# SAM4S_MCU_Hat.net
KiCad netlist of a schematic drawn in Altium Designer
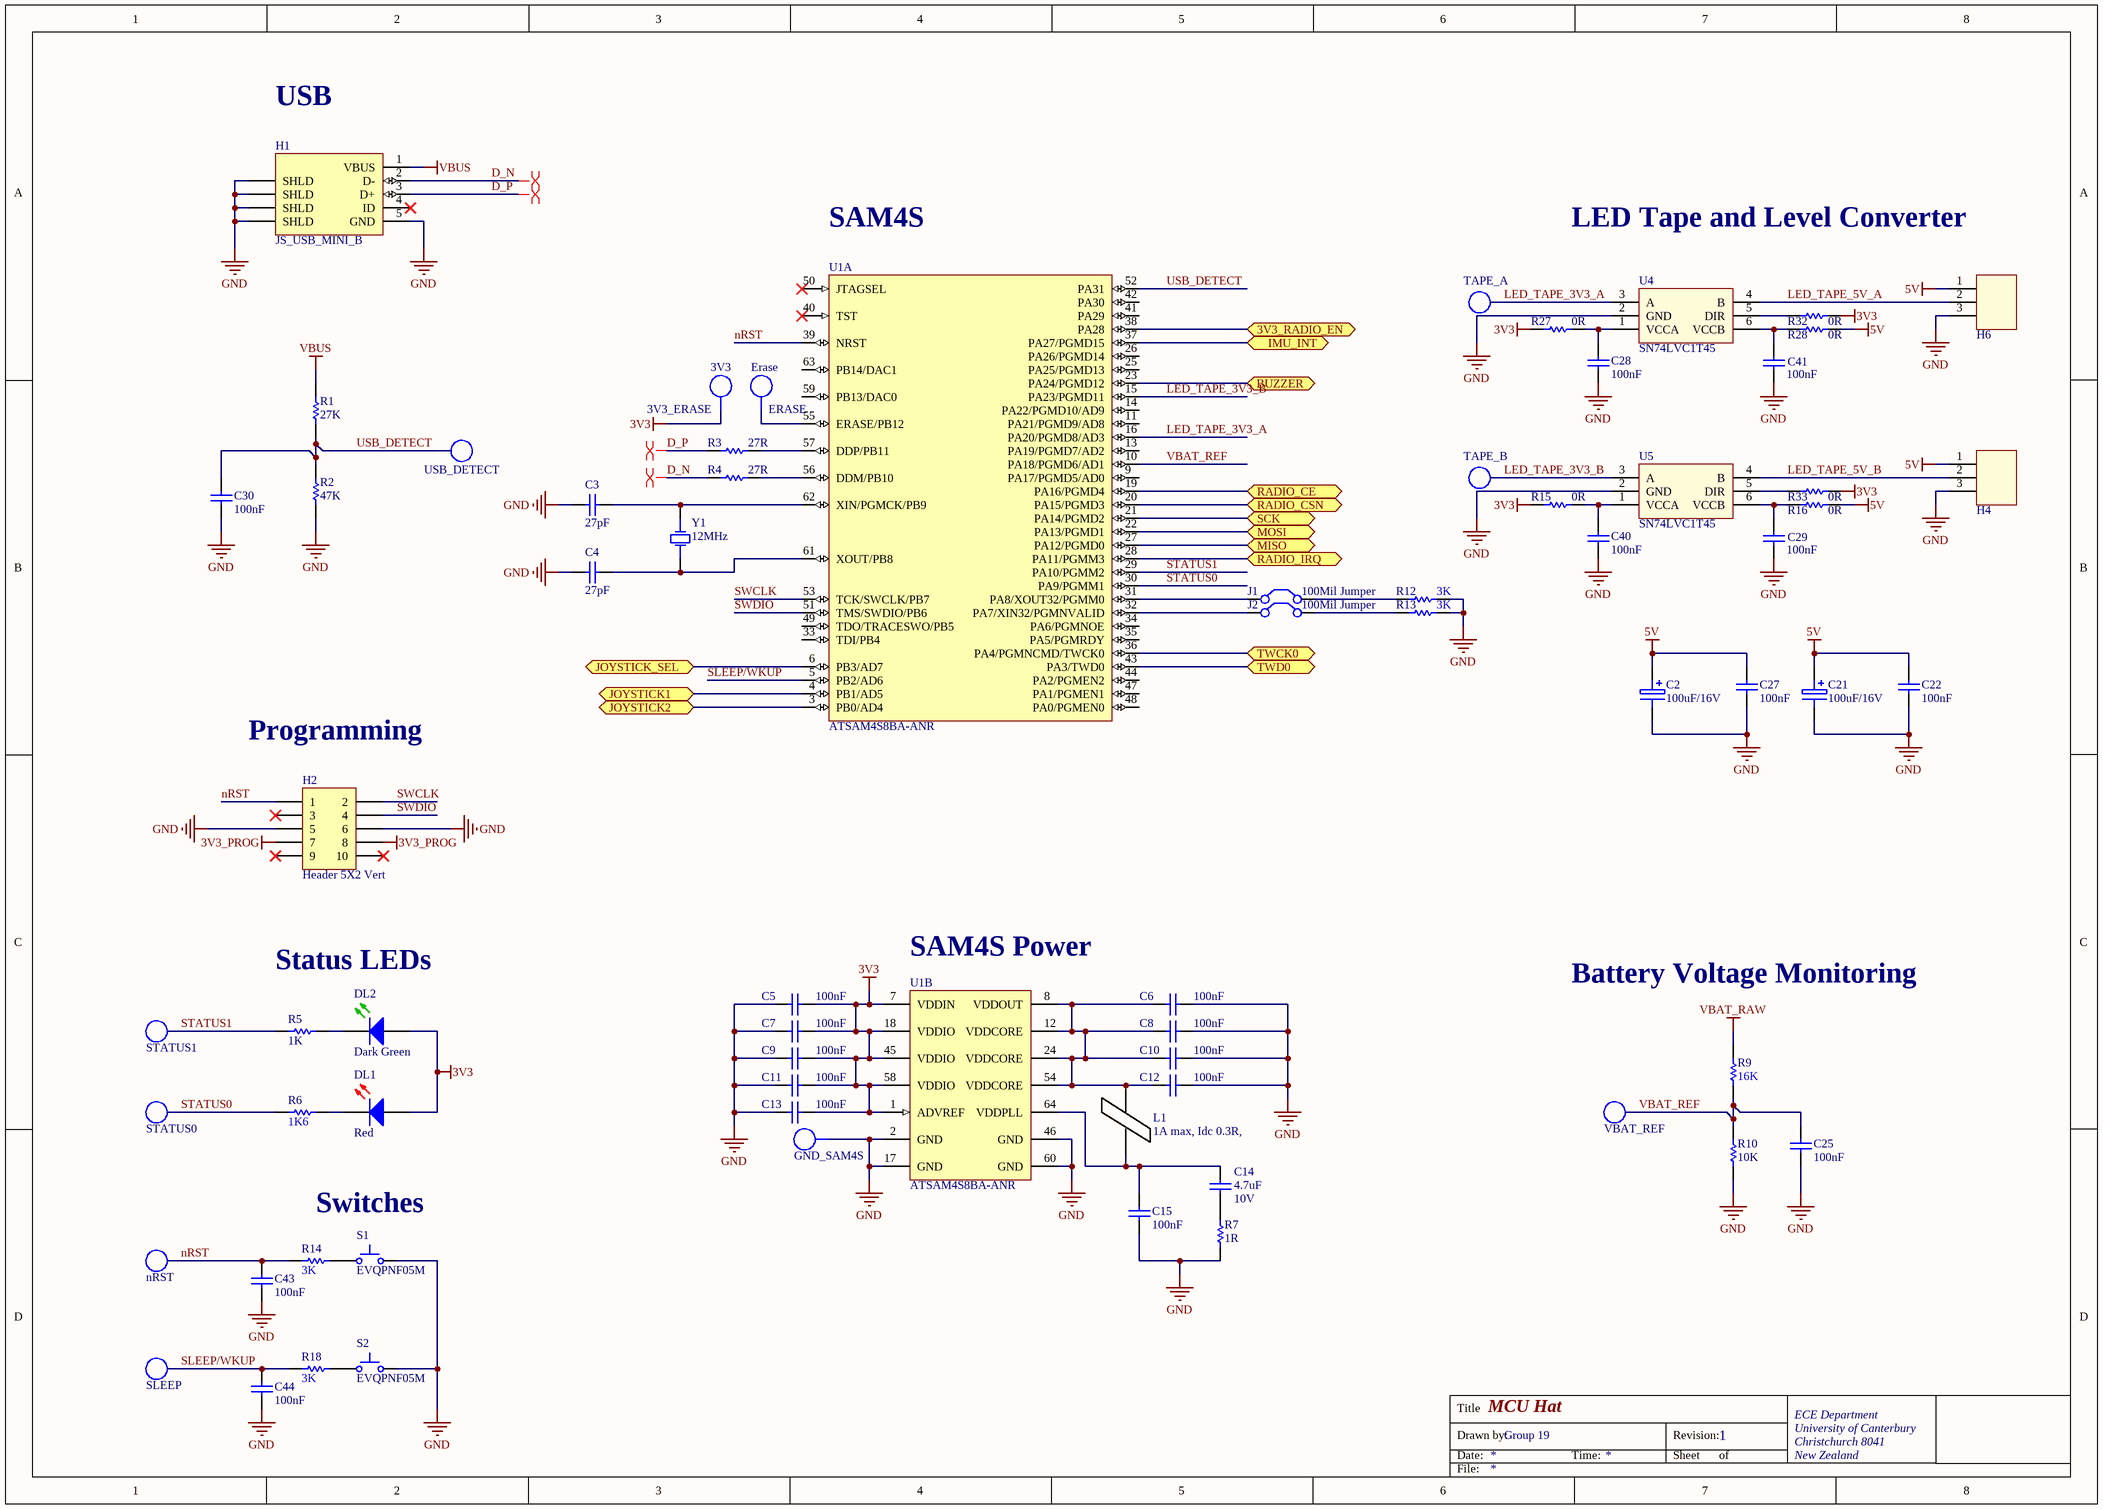
[diagram p0: SAM4S_MCU_Hat.SchDoc]

(export (version "E")
  (design (tool "Eeschema 10.0.6"))
  (components
    (comp (ref "3V3_ERASE")
      (value "3V3")
      (footprint "TP_1206")
      (description "Test-Point 3.3x1.6x2.1mm SMD")
      (fields
        (field (name "MANUFACTURER") "Harwin Inc")
        (field (name "MANUFACTURER PART NUMBER") "S1751-46R")
      )
      (libsource (lib "ECE AD19Components_19V1") (part "TP_1206"))
    )
    (comp (ref "C2")
      (value "100uF/16V")
      (footprint "NICH-1")
      (description "CAP ALUM 100uF 16V SMD")
      (fields (field (name "MANUFACTURER") "Nichcon"))
      (libsource (lib "ECE AD19Components_19V1") (part "CA_100uF_16V"))
    )
    (comp (ref "C3")
      (value "27pF")
      (footprint "CAPC1608L")
      (description "CAP CER 27pF NPO/COG +-5% 50V 0603")
      (libsource (lib "ECE AD19Components_19V1") (part "CC_27pF_0603"))
    )
    (comp (ref "C4")
      (value "27pF")
      (footprint "CAPC1608L")
      (description "CAP CER 27pF NPO/COG +-5% 50V 0603")
      (libsource (lib "ECE AD19Components_19V1") (part "CC_27pF_0603"))
    )
    (comp (ref "C5")
      (value "100nF")
      (footprint "CAPC1608L")
      (description "CAP CER 100nF X7R +-10% 50V 0603")
      (libsource (lib "ECE AD19Components_19V1") (part "CC_100nF_0603"))
    )
    (comp (ref "C6")
      (value "100nF")
      (footprint "CAPC1608L")
      (description "CAP CER 100nF X7R +-10% 50V 0603")
      (libsource (lib "ECE AD19Components_19V1") (part "CC_100nF_0603"))
    )
    (comp (ref "C7")
      (value "100nF")
      (footprint "CAPC1608L")
      (description "CAP CER 100nF X7R +-10% 50V 0603")
      (libsource (lib "ECE AD19Components_19V1") (part "CC_100nF_0603"))
    )
    (comp (ref "C8")
      (value "100nF")
      (footprint "CAPC1608L")
      (description "CAP CER 100nF X7R +-10% 50V 0603")
      (libsource (lib "ECE AD19Components_19V1") (part "CC_100nF_0603"))
    )
    (comp (ref "C9")
      (value "100nF")
      (footprint "CAPC1608L")
      (description "CAP CER 100nF X7R +-10% 50V 0603")
      (libsource (lib "ECE AD19Components_19V1") (part "CC_100nF_0603"))
    )
    (comp (ref "C10")
      (value "100nF")
      (footprint "CAPC1608L")
      (description "CAP CER 100nF X7R +-10% 50V 0603")
      (libsource (lib "ECE AD19Components_19V1") (part "CC_100nF_0603"))
    )
    (comp (ref "C11")
      (value "100nF")
      (footprint "CAPC1608L")
      (description "CAP CER 100nF X7R +-10% 50V 0603")
      (libsource (lib "ECE AD19Components_19V1") (part "CC_100nF_0603"))
    )
    (comp (ref "C12")
      (value "100nF")
      (footprint "CAPC1608L")
      (description "CAP CER 100nF X7R +-10% 50V 0603")
      (libsource (lib "ECE AD19Components_19V1") (part "CC_100nF_0603"))
    )
    (comp (ref "C13")
      (value "100nF")
      (footprint "CAPC1608L")
      (description "CAP CER 100nF X7R +-10% 50V 0603")
      (libsource (lib "ECE AD19Components_19V1") (part "CC_100nF_0603"))
    )
    (comp (ref "C14")
      (value "4.7uF")
      (footprint "CAPC1608N")
      (description "CAP CER 4.7uF X5R +-20%  10V 0603")
      (fields (field (name "MAX VOLTAGE") "10V"))
      (libsource (lib "ECE AD19Components_19V1") (part "CC_4.7uF_0603"))
    )
    (comp (ref "C15")
      (value "100nF")
      (footprint "CAPC1608L")
      (description "CAP CER 100nF X7R +-10% 50V 0603")
      (libsource (lib "ECE AD19Components_19V1") (part "CC_100nF_0603"))
    )
    (comp (ref "C21")
      (value "100uF/16V")
      (footprint "NICH-1")
      (description "CAP ALUM 100uF 16V SMD")
      (fields (field (name "MANUFACTURER") "Nichcon"))
      (libsource (lib "ECE AD19Components_19V1") (part "CA_100uF_16V"))
    )
    (comp (ref "C22")
      (value "100nF")
      (footprint "CAPC1608L")
      (description "CAP CER 100nF X7R +-10% 50V 0603")
      (libsource (lib "ECE AD19Components_19V1") (part "CC_100nF_0603"))
    )
    (comp (ref "C25")
      (value "100nF")
      (footprint "CAPC1608L")
      (description "CAP CER 100nF X7R +-10% 50V 0603")
      (libsource (lib "ECE AD19Components_19V1") (part "CC_100nF_0603"))
    )
    (comp (ref "C27")
      (value "100nF")
      (footprint "CAPC1608L")
      (description "CAP CER 100nF X7R +-10% 50V 0603")
      (libsource (lib "ECE AD19Components_19V1") (part "CC_100nF_0603"))
    )
    (comp (ref "C28")
      (value "100nF")
      (footprint "CAPC1608L")
      (description "CAP CER 100nF X7R +-10% 50V 0603")
      (libsource (lib "ECE AD19Components_19V1") (part "CC_100nF_0603"))
    )
    (comp (ref "C29")
      (value "100nF")
      (footprint "CAPC1608L")
      (description "CAP CER 100nF X7R +-10% 50V 0603")
      (libsource (lib "ECE AD19Components_19V1") (part "CC_100nF_0603"))
    )
    (comp (ref "C30")
      (value "100nF")
      (footprint "CAPC1608L")
      (description "CAP CER 100nF X7R +-10% 50V 0603")
      (libsource (lib "ECE AD19Components_19V1") (part "CC_100nF_0603"))
    )
    (comp (ref "C40")
      (value "100nF")
      (footprint "CAPC1608L")
      (description "CAP CER 100nF X7R +-10% 50V 0603")
      (libsource (lib "ECE AD19Components_19V1") (part "CC_100nF_0603"))
    )
    (comp (ref "C41")
      (value "100nF")
      (footprint "CAPC1608L")
      (description "CAP CER 100nF X7R +-10% 50V 0603")
      (libsource (lib "ECE AD19Components_19V1") (part "CC_100nF_0603"))
    )
    (comp (ref "C43")
      (value "100nF")
      (footprint "CAPC1608L")
      (description "CAP CER 100nF X7R +-10% 50V 0603")
      (libsource (lib "ECE AD19Components_19V1") (part "CC_100nF_0603"))
    )
    (comp (ref "C44")
      (value "100nF")
      (footprint "CAPC1608L")
      (description "CAP CER 100nF X7R +-10% 50V 0603")
      (libsource (lib "ECE AD19Components_19V1") (part "CC_100nF_0603"))
    )
    (comp (ref "DL1")
      (value "Red")
      (footprint "WL-SMCW0603")
      (description "LED Red 250mcd 0603 SMD")
      (fields
        (field (name "MANUFACTURER") "WURTH ELEKTRONIK")
        (field (name "MANUFACTURER PART NUMBER") "150060RS75000")
        (field (name "LED COLOUR") "Red")
      )
      (libsource (lib "ECE AD19Components_19V1") (part "DL_150060RS75000"))
    )
    (comp (ref "DL2")
      (value "Dark Green")
      (footprint "WL-SMCW0603")
      (description "LED Dk Green 430mcd 0603 SMD")
      (fields
        (field (name "MANUFACTURER") "WURTH ELEKTRONIK")
        (field (name "MANUFACTURER PART NUMBER") "150060GS75000")
        (field (name "LED COLOUR") "Dark Green")
      )
      (libsource (lib "ECE AD19Components_19V1") (part "DL_150060GS75000"))
    )
    (comp (ref "ERASE")
      (value "Erase")
      (footprint "TP_1206")
      (description "Test-Point 3.3x1.6x2.1mm SMD")
      (fields
        (field (name "MANUFACTURER") "Harwin Inc")
        (field (name "MANUFACTURER PART NUMBER") "S1751-46R")
      )
      (libsource (lib "ECE AD19Components_19V1") (part "TP_1206"))
    )
    (comp (ref "GND_SAM4S")
      (value "TP")
      (footprint "TP_1206")
      (description "Test-Point 3.3x1.6x2.1mm SMD")
      (fields
        (field (name "MANUFACTURER") "Harwin Inc")
        (field (name "MANUFACTURER PART NUMBER") "S1751-46R")
      )
      (libsource (lib "ECE AD19Components_19V1") (part "TP_1206"))
    )
    (comp (ref "H1")
      (value "JS_USB_MINI_B")
      (footprint "USB/SM0.8-6H5")
      (description "USB 2.0, Right Angle, SMT, B Type, Receptacle, 5 Position,")
      (fields (field (name "MANUFACTURER") "FCI"))
      (libsource (lib "ECE AD19Components_19V1") (part "JS_USB_MINI_B_SMT"))
    )
    (comp (ref "H2")
      (value "Header 5X2 Vert")
      (footprint "IDC2.54-V10D")
      (description "IDC Header, 2,54mm, 10-Pin, Vert")
      (libsource (lib "ECE AD19Components_19V1") (part "JA_HDR_IDC_5X2_VERT"))
    )
    (comp (ref "H4")
      (value "HEADER_3")
      (footprint "HEADER_3POS")
      (description "3Pin Header 2.54mm spacing")
      (libsource (lib "ENCE461AD19_19V2") (part "HEADER_3"))
    )
    (comp (ref "H6")
      (value "HEADER_3")
      (footprint "HEADER_3POS")
      (description "3Pin Header 2.54mm spacing")
      (libsource (lib "ENCE461AD19_19V2") (part "HEADER_3"))
    )
    (comp (ref "J1")
      (value "100Mil Jumper")
      (footprint "JMP2.54")
      (description "2.54mm Jumper Thru Hole")
      (libsource (lib "ECE AD19Components_19V1") (part "TP_JUMPER"))
    )
    (comp (ref "J2")
      (value "100Mil Jumper")
      (footprint "JMP2.54")
      (description "2.54mm Jumper Thru Hole")
      (libsource (lib "ECE AD19Components_19V1") (part "TP_JUMPER"))
    )
    (comp (ref "L1")
      (value "1A max, Idc 0.3R,")
      (footprint "INDC3216L")
      (description "Ferrite Bead, Rdc 0.3R, Z100MHZ 600R, Imax 1A, SMD 1206")
      (fields
        (field (name "MANUFACTURER") "FAIR-RITE")
        (field (name "MANUFACTURER PART NUMBER") "2512066017Y1")
      )
      (libsource (lib "ECE AD19Components_19V1") (part "IN_Ferrite-Bead"))
    )
    (comp (ref "nRST")
      (value "TP_0603")
      (footprint "TP_0603")
      (description "Test Point 1.65X0.9X1.2mm SMD")
      (fields
        (field (name "MANUFACTURER") "TE Connectivity AMP Connectors")
        (field (name "MANUFACTURER PART NUMBER") "1625854-3")
      )
      (libsource (lib "ECE AD19Components_19V1") (part "TP_0603"))
    )
    (comp (ref "R1")
      (value "27K")
      (footprint "RESC1608L")
      (description "RES 27K OHM 1/10W 5% 0603 SMD")
      (libsource (lib "ECE AD19Components_19V1") (part "RS_27K"))
    )
    (comp (ref "R2")
      (value "47K")
      (footprint "RESC1608N")
      (description "RES 47.0K OHM 1/10W 5% 0603 SMD")
      (libsource (lib "ECE AD19Components_19V1") (part "RS_47K"))
    )
    (comp (ref "R3")
      (value "27R")
      (footprint "RESC1608L")
      (description "RES 27 OHM 1/10W 5% 0603 SMD")
      (libsource (lib "ECE AD19Components_19V1") (part "RS_27R"))
    )
    (comp (ref "R4")
      (value "27R")
      (footprint "RESC1608L")
      (description "RES 27 OHM 1/10W 5% 0603 SMD")
      (libsource (lib "ECE AD19Components_19V1") (part "RS_27R"))
    )
    (comp (ref "R5")
      (value "1K")
      (footprint "RESC1608L")
      (description "RES 1.0K OHM 1/10W 5% 0603 SMD")
      (libsource (lib "ECE AD19Components_19V1") (part "RS_1K"))
    )
    (comp (ref "R6")
      (value "1K6")
      (footprint "RESC1608L")
      (description "RES 1.6K OHM 1/10W 5% 0603 SMD")
      (libsource (lib "ECE AD19Components_19V1") (part "RS_1K6"))
    )
    (comp (ref "R7")
      (value "1R")
      (footprint "RESC3216L")
      (description "RES 1R OHM 1/4W 5% 1206 SMD")
      (libsource (lib "ECE AD19Components_19V1") (part "RT_1R"))
    )
    (comp (ref "R9")
      (value "16K")
      (footprint "RESC1608L")
      (description "RES 16K OHM 1/10W 5% 0603 SMD")
      (libsource (lib "ECE AD19Components_19V1") (part "RS_16K"))
    )
    (comp (ref "R10")
      (value "10K")
      (footprint "RESC1608L")
      (description "RES 10.0K OHM 1/10W 5% 0603 SMD")
      (libsource (lib "ECE AD19Components_19V1") (part "RS_10K"))
    )
    (comp (ref "R12")
      (value "3K")
      (footprint "RESC1608L")
      (description "RES 3K OHM 1/10W 5% 0603 SMD")
      (libsource (lib "ECE AD19Components_19V1") (part "RS_3K"))
    )
    (comp (ref "R13")
      (value "3K")
      (footprint "RESC1608L")
      (description "RES 3K OHM 1/10W 5% 0603 SMD")
      (libsource (lib "ECE AD19Components_19V1") (part "RS_3K"))
    )
    (comp (ref "R14")
      (value "3K")
      (footprint "RESC1608L")
      (description "RES 3K OHM 1/10W 5% 0603 SMD")
      (libsource (lib "ECE AD19Components_19V1") (part "RS_3K"))
    )
    (comp (ref "R15")
      (value "0R")
      (footprint "RESC1608L")
      (description "RES 0.0 OHM 1/10W 5% 0603 SMD")
      (libsource (lib "ECE AD19Components_19V1") (part "RS_0R0"))
    )
    (comp (ref "R16")
      (value "0R")
      (footprint "RESC1608L")
      (description "RES 0.0 OHM 1/10W 5% 0603 SMD")
      (libsource (lib "ECE AD19Components_19V1") (part "RS_0R0"))
    )
    (comp (ref "R18")
      (value "3K")
      (footprint "RESC1608L")
      (description "RES 3K OHM 1/10W 5% 0603 SMD")
      (libsource (lib "ECE AD19Components_19V1") (part "RS_3K"))
    )
    (comp (ref "R27")
      (value "0R")
      (footprint "RESC1608L")
      (description "RES 0.0 OHM 1/10W 5% 0603 SMD")
      (libsource (lib "ECE AD19Components_19V1") (part "RS_0R0"))
    )
    (comp (ref "R28")
      (value "0R")
      (footprint "RESC1608L")
      (description "RES 0.0 OHM 1/10W 5% 0603 SMD")
      (libsource (lib "ECE AD19Components_19V1") (part "RS_0R0"))
    )
    (comp (ref "R32")
      (value "0R")
      (footprint "RESC1608L")
      (description "RES 0.0 OHM 1/10W 5% 0603 SMD")
      (libsource (lib "ECE AD19Components_19V1") (part "RS_0R0"))
    )
    (comp (ref "R33")
      (value "0R")
      (footprint "RESC1608L")
      (description "RES 0.0 OHM 1/10W 5% 0603 SMD")
      (libsource (lib "ECE AD19Components_19V1") (part "RS_0R0"))
    )
    (comp (ref "S1")
      (value "EVQPNF05M")
      (footprint "EVQPNF05M")
      (description "Panasonic 6 x 3.5mm SMD Light Touch Switch Type SMD")
      (fields (field (name "MANUFACTURER") "Panasonic"))
      (libsource (lib "ECE AD19Components_19V1") (part "WS_EVQPNF05M"))
    )
    (comp (ref "S2")
      (value "EVQPNF05M")
      (footprint "EVQPNF05M")
      (description "Panasonic 6 x 3.5mm SMD Light Touch Switch Type SMD")
      (fields (field (name "MANUFACTURER") "Panasonic"))
      (libsource (lib "ECE AD19Components_19V1") (part "WS_EVQPNF05M"))
    )
    (comp (ref "SLEEP")
      (value "TP_0603")
      (footprint "TP_0603")
      (description "Test Point 1.65X0.9X1.2mm SMD")
      (fields
        (field (name "MANUFACTURER") "TE Connectivity AMP Connectors")
        (field (name "MANUFACTURER PART NUMBER") "1625854-3")
      )
      (libsource (lib "ECE AD19Components_19V1") (part "TP_0603"))
    )
    (comp (ref "STATUS0")
      (value "TP_0603")
      (footprint "TP_0603")
      (description "Test Point 1.65X0.9X1.2mm SMD")
      (fields
        (field (name "MANUFACTURER") "TE Connectivity AMP Connectors")
        (field (name "MANUFACTURER PART NUMBER") "1625854-3")
      )
      (libsource (lib "ECE AD19Components_19V1") (part "TP_0603"))
    )
    (comp (ref "STATUS1")
      (value "TP_0603")
      (footprint "TP_0603")
      (description "Test Point 1.65X0.9X1.2mm SMD")
      (fields
        (field (name "MANUFACTURER") "TE Connectivity AMP Connectors")
        (field (name "MANUFACTURER PART NUMBER") "1625854-3")
      )
      (libsource (lib "ECE AD19Components_19V1") (part "TP_0603"))
    )
    (comp (ref "TAPE_A")
      (value "TP_0603")
      (footprint "TP_0603")
      (description "Test Point 1.65X0.9X1.2mm SMD")
      (fields
        (field (name "MANUFACTURER") "TE Connectivity AMP Connectors")
        (field (name "MANUFACTURER PART NUMBER") "1625854-3")
      )
      (libsource (lib "ECE AD19Components_19V1") (part "TP_0603"))
    )
    (comp (ref "TAPE_B")
      (value "TP_0603")
      (footprint "TP_0603")
      (description "Test Point 1.65X0.9X1.2mm SMD")
      (fields
        (field (name "MANUFACTURER") "TE Connectivity AMP Connectors")
        (field (name "MANUFACTURER PART NUMBER") "1625854-3")
      )
      (libsource (lib "ECE AD19Components_19V1") (part "TP_0603"))
    )
    (comp (ref "U1")
      (value "ATSAM4S8BA-ANR")
      (footprint "LQFP64_L")
      (description "IC MCU 32BIT 512KB FLASH 64LQFP")
      (fields (field (name "MANUFACTURER") "Atmel"))
      (libsource (lib "ECE AD19Components_19V1") (part "SE_ATSAM4S16BA-MU"))
    )
    (comp (ref "U4")
      (value "SN74LVC1T45")
      (footprint "SOT23-6_N")
      (description "1.8V - 5V level converter")
      (libsource (lib "ENCE461_extras_2020") (part "SN74LVC1T45"))
    )
    (comp (ref "U5")
      (value "SN74LVC1T45")
      (footprint "SOT23-6_N")
      (description "1.8V - 5V level converter")
      (libsource (lib "ENCE461_extras_2020") (part "SN74LVC1T45"))
    )
    (comp (ref "USB_DETECT")
      (value "TP_0603")
      (footprint "TP_0603")
      (description "Test Point 1.65X0.9X1.2mm SMD")
      (fields
        (field (name "MANUFACTURER") "TE Connectivity AMP Connectors")
        (field (name "MANUFACTURER PART NUMBER") "1625854-3")
      )
      (libsource (lib "ECE AD19Components_19V1") (part "TP_0603"))
    )
    (comp (ref "VBAT_REF")
      (value "TP_0603")
      (footprint "TP_0603")
      (description "Test Point 1.65X0.9X1.2mm SMD")
      (fields
        (field (name "MANUFACTURER") "TE Connectivity AMP Connectors")
        (field (name "MANUFACTURER PART NUMBER") "1625854-3")
      )
      (libsource (lib "ECE AD19Components_19V1") (part "TP_0603"))
    )
    (comp (ref "Y1")
      (value "12MHz")
      (footprint "6.0X3.5-4")
      (description "CRYSTAL 12MHZ 18PF 6X3.5mm SMD")
      (fields
        (field (name "MANUFACTURER") "CTS-Frequency Controls")
        (field (name "MANUFACTURER PART NUMBER") "406C35D12M00000")
        (field (name "FREQUENCY") "12MHz")
      )
      (libsource (lib "ECE AD19Components_19V1") (part "XT_CRYSTAL_12MHz_18pF"))
    )
  )
  (nets
    (net (code "1") (name "/3V3_RADIO_EN") (class "Default")
      (node (ref "U1") (pin "38") (pinfunction "PA28_38") (pintype "bidirectional"))
    )
    (net (code "2") (name "/BUZZER") (class "Default")
      (node (ref "U1") (pin "23") (pinfunction "PA24/PGMD12_23") (pintype "bidirectional"))
    )
    (net (code "3") (name "/D_N") (class "Default")
      (node (ref "H1") (pin "2") (pinfunction "D-_2") (pintype "bidirectional"))
      (node (ref "R4") (pin "1") (pinfunction "1_1") (pintype "passive"))
    )
    (net (code "4") (name "/D_P") (class "Default")
      (node (ref "H1") (pin "3") (pinfunction "D+_3") (pintype "bidirectional"))
      (node (ref "R3") (pin "1") (pinfunction "1_1") (pintype "passive"))
    )
    (net (code "5") (name "/IMU_INT") (class "Default")
      (node (ref "U1") (pin "37") (pinfunction "PA27/PGMD15_37") (pintype "bidirectional"))
    )
    (net (code "6") (name "/JOYSTICK1") (class "Default")
      (node (ref "U1") (pin "4") (pinfunction "PB1/AD5_4") (pintype "bidirectional"))
    )
    (net (code "7") (name "/JOYSTICK2") (class "Default")
      (node (ref "U1") (pin "3") (pinfunction "PB0/AD4_3") (pintype "bidirectional"))
    )
    (net (code "8") (name "/JOYSTICK_SEL") (class "Default")
      (node (ref "U1") (pin "6") (pinfunction "PB3/AD7_6") (pintype "bidirectional"))
    )
    (net (code "9") (name "/LED_TAPE_3V3_A") (class "Default")
      (node (ref "TAPE_A") (pin "1") (pinfunction "TP_1") (pintype "passive"))
      (node (ref "U1") (pin "16") (pinfunction "PA20/PGMD8/AD3_16") (pintype "bidirectional"))
      (node (ref "U4") (pin "3") (pinfunction "A_3") (pintype "passive"))
    )
    (net (code "10") (name "/LED_TAPE_3V3_B") (class "Default")
      (node (ref "TAPE_B") (pin "1") (pinfunction "TP_1") (pintype "passive"))
      (node (ref "U1") (pin "15") (pinfunction "PA23/PGMD11_15") (pintype "bidirectional"))
      (node (ref "U5") (pin "3") (pinfunction "A_3") (pintype "passive"))
    )
    (net (code "11") (name "/LED_TAPE_5V_A") (class "Default")
      (node (ref "H6") (pin "2") (pintype "passive"))
      (node (ref "U4") (pin "4") (pinfunction "B_4") (pintype "passive"))
    )
    (net (code "12") (name "/LED_TAPE_5V_B") (class "Default")
      (node (ref "H4") (pin "2") (pintype "passive"))
      (node (ref "U5") (pin "4") (pinfunction "B_4") (pintype "passive"))
    )
    (net (code "13") (name "/MISO") (class "Default")
      (node (ref "U1") (pin "27") (pinfunction "PA12/PGMD0_27") (pintype "bidirectional"))
    )
    (net (code "14") (name "/MOSI") (class "Default")
      (node (ref "U1") (pin "22") (pinfunction "PA13/PGMD1_22") (pintype "bidirectional"))
    )
    (net (code "15") (name "/RADIO_CE") (class "Default")
      (node (ref "U1") (pin "19") (pinfunction "PA16/PGMD4_19") (pintype "bidirectional"))
    )
    (net (code "16") (name "/RADIO_CSN") (class "Default")
      (node (ref "U1") (pin "20") (pinfunction "PA15/PGMD3_20") (pintype "bidirectional"))
    )
    (net (code "17") (name "/RADIO_IRQ") (class "Default")
      (node (ref "U1") (pin "28") (pinfunction "PA11/PGMM3_28") (pintype "bidirectional"))
    )
    (net (code "18") (name "/SCK") (class "Default")
      (node (ref "U1") (pin "21") (pinfunction "PA14/PGMD2_21") (pintype "bidirectional"))
    )
    (net (code "19") (name "/SLEEP{slash}WKUP") (class "Default")
      (node (ref "C44") (pin "2") (pinfunction "2_2") (pintype "passive"))
      (node (ref "R18") (pin "1") (pinfunction "1_1") (pintype "passive"))
      (node (ref "SLEEP") (pin "1") (pinfunction "TP_1") (pintype "passive"))
      (node (ref "U1") (pin "5") (pinfunction "PB2/AD6_5") (pintype "bidirectional"))
    )
    (net (code "20") (name "/STATUS0") (class "Default")
      (node (ref "R6") (pin "1") (pinfunction "1_1") (pintype "passive"))
      (node (ref "STATUS0") (pin "1") (pinfunction "TP_1") (pintype "passive"))
      (node (ref "U1") (pin "30") (pinfunction "PA9/PGMM1_30") (pintype "bidirectional"))
    )
    (net (code "21") (name "/STATUS1") (class "Default")
      (node (ref "R5") (pin "1") (pinfunction "1_1") (pintype "passive"))
      (node (ref "STATUS1") (pin "1") (pinfunction "TP_1") (pintype "passive"))
      (node (ref "U1") (pin "29") (pinfunction "PA10/PGMM2_29") (pintype "bidirectional"))
    )
    (net (code "22") (name "/SWCLK") (class "Default")
      (node (ref "H2") (pin "2") (pinfunction "2_2") (pintype "passive"))
      (node (ref "U1") (pin "53") (pinfunction "TCK/SWCLK/PB7_53") (pintype "bidirectional"))
    )
    (net (code "23") (name "/SWDIO") (class "Default")
      (node (ref "H2") (pin "4") (pinfunction "4_4") (pintype "passive"))
      (node (ref "U1") (pin "51") (pinfunction "TMS/SWDIO/PB6_51") (pintype "bidirectional"))
    )
    (net (code "24") (name "/TWCK0") (class "Default")
      (node (ref "U1") (pin "36") (pinfunction "PA4/PGMNCMD/TWCK0_36") (pintype "bidirectional"))
    )
    (net (code "25") (name "/TWD0") (class "Default")
      (node (ref "U1") (pin "43") (pinfunction "PA3/TWD0_43") (pintype "bidirectional"))
    )
    (net (code "26") (name "/USB_DETECT") (class "Default")
      (node (ref "C30") (pin "2") (pinfunction "2_2") (pintype "passive"))
      (node (ref "R1") (pin "1") (pinfunction "1_1") (pintype "passive"))
      (node (ref "R2") (pin "2") (pinfunction "2_2") (pintype "passive"))
      (node (ref "U1") (pin "52") (pinfunction "PA31_52") (pintype "bidirectional"))
      (node (ref "USB_DETECT") (pin "1") (pinfunction "TP_1") (pintype "passive"))
    )
    (net (code "27") (name "/VBAT_REF") (class "Default")
      (node (ref "C25") (pin "2") (pinfunction "2_2") (pintype "passive"))
      (node (ref "R10") (pin "2") (pinfunction "2_2") (pintype "passive"))
      (node (ref "R9") (pin "1") (pinfunction "1_1") (pintype "passive"))
      (node (ref "U1") (pin "10") (pinfunction "PA18/PGMD6/AD1_10") (pintype "bidirectional"))
      (node (ref "VBAT_REF") (pin "1") (pinfunction "TP_1") (pintype "passive"))
    )
    (net (code "28") (name "/nRST") (class "Default")
      (node (ref "C43") (pin "2") (pinfunction "2_2") (pintype "passive"))
      (node (ref "H2") (pin "1") (pinfunction "1_1") (pintype "passive"))
      (node (ref "R14") (pin "1") (pinfunction "1_1") (pintype "passive"))
      (node (ref "U1") (pin "39") (pinfunction "NRST_39") (pintype "bidirectional"))
      (node (ref "nRST") (pin "1") (pinfunction "TP_1") (pintype "passive"))
    )
    (net (code "29") (name "3V3") (class "Default")
      (node (ref "3V3_ERASE") (pin "1") (pinfunction "1_1") (pintype "passive"))
      (node (ref "C11") (pin "2") (pinfunction "2_2") (pintype "passive"))
      (node (ref "C13") (pin "2") (pinfunction "2_2") (pintype "passive"))
      (node (ref "C5") (pin "2") (pinfunction "2_2") (pintype "passive"))
      (node (ref "C7") (pin "2") (pinfunction "2_2") (pintype "passive"))
      (node (ref "C9") (pin "2") (pinfunction "2_2") (pintype "passive"))
      (node (ref "DL1") (pin "2") (pinfunction "A_2") (pintype "passive"))
      (node (ref "DL2") (pin "2") (pinfunction "A_2") (pintype "passive"))
      (node (ref "R15") (pin "1") (pinfunction "1_1") (pintype "passive"))
      (node (ref "R27") (pin "1") (pinfunction "1_1") (pintype "passive"))
      (node (ref "R32") (pin "2") (pinfunction "2_2") (pintype "passive"))
      (node (ref "R33") (pin "2") (pinfunction "2_2") (pintype "passive"))
      (node (ref "U1") (pin "1") (pinfunction "ADVREF_1") (pintype "input"))
      (node (ref "U1") (pin "18") (pinfunction "VDDIO_18") (pintype "power_in"))
      (node (ref "U1") (pin "45") (pinfunction "VDDIO_45") (pintype "power_in"))
      (node (ref "U1") (pin "58") (pinfunction "VDDIO_58") (pintype "power_in"))
      (node (ref "U1") (pin "7") (pinfunction "VDDIN_7") (pintype "power_in"))
    )
    (net (code "30") (name "3V3_PROG") (class "Default")
      (node (ref "H2") (pin "7") (pinfunction "7_7") (pintype "passive"))
      (node (ref "H2") (pin "8") (pinfunction "8_8") (pintype "passive"))
    )
    (net (code "31") (name "5V") (class "Default")
      (node (ref "C2") (pin "2") (pintype "passive"))
      (node (ref "C21") (pin "2") (pintype "passive"))
      (node (ref "C22") (pin "2") (pinfunction "2_2") (pintype "passive"))
      (node (ref "C27") (pin "2") (pinfunction "2_2") (pintype "passive"))
      (node (ref "H4") (pin "1") (pintype "passive"))
      (node (ref "H6") (pin "1") (pintype "passive"))
      (node (ref "R16") (pin "2") (pinfunction "2_2") (pintype "passive"))
      (node (ref "R28") (pin "2") (pinfunction "2_2") (pintype "passive"))
    )
    (net (code "32") (name "GND") (class "Default")
      (node (ref "C10") (pin "2") (pinfunction "2_2") (pintype "passive"))
      (node (ref "C11") (pin "1") (pinfunction "1_1") (pintype "passive"))
      (node (ref "C12") (pin "2") (pinfunction "2_2") (pintype "passive"))
      (node (ref "C13") (pin "1") (pinfunction "1_1") (pintype "passive"))
      (node (ref "C15") (pin "2") (pinfunction "2_2") (pintype "passive"))
      (node (ref "C2") (pin "1") (pintype "passive"))
      (node (ref "C21") (pin "1") (pintype "passive"))
      (node (ref "C22") (pin "1") (pinfunction "1_1") (pintype "passive"))
      (node (ref "C25") (pin "1") (pinfunction "1_1") (pintype "passive"))
      (node (ref "C27") (pin "1") (pinfunction "1_1") (pintype "passive"))
      (node (ref "C28") (pin "1") (pinfunction "1_1") (pintype "passive"))
      (node (ref "C29") (pin "1") (pinfunction "1_1") (pintype "passive"))
      (node (ref "C3") (pin "1") (pinfunction "1_1") (pintype "passive"))
      (node (ref "C30") (pin "1") (pinfunction "1_1") (pintype "passive"))
      (node (ref "C4") (pin "1") (pinfunction "1_1") (pintype "passive"))
      (node (ref "C40") (pin "1") (pinfunction "1_1") (pintype "passive"))
      (node (ref "C41") (pin "1") (pinfunction "1_1") (pintype "passive"))
      (node (ref "C43") (pin "1") (pinfunction "1_1") (pintype "passive"))
      (node (ref "C44") (pin "1") (pinfunction "1_1") (pintype "passive"))
      (node (ref "C5") (pin "1") (pinfunction "1_1") (pintype "passive"))
      (node (ref "C6") (pin "2") (pinfunction "2_2") (pintype "passive"))
      (node (ref "C7") (pin "1") (pinfunction "1_1") (pintype "passive"))
      (node (ref "C8") (pin "2") (pinfunction "2_2") (pintype "passive"))
      (node (ref "C9") (pin "1") (pinfunction "1_1") (pintype "passive"))
      (node (ref "GND_SAM4S") (pin "1") (pinfunction "1_1") (pintype "passive"))
      (node (ref "H1") (pin "5") (pinfunction "GND_5") (pintype "passive"))
      (node (ref "H1") (pin "6") (pinfunction "SHLD_6") (pintype "passive"))
      (node (ref "H1") (pin "7") (pinfunction "SHLD_7") (pintype "passive"))
      (node (ref "H1") (pin "8") (pinfunction "SHLD_8") (pintype "passive"))
      (node (ref "H1") (pin "9") (pinfunction "SHLD_9") (pintype "passive"))
      (node (ref "H2") (pin "5") (pinfunction "5_5") (pintype "passive"))
      (node (ref "H2") (pin "6") (pinfunction "6_6") (pintype "passive"))
      (node (ref "H4") (pin "3") (pintype "passive"))
      (node (ref "H6") (pin "3") (pintype "passive"))
      (node (ref "R10") (pin "1") (pinfunction "1_1") (pintype "passive"))
      (node (ref "R12") (pin "2") (pinfunction "2_2") (pintype "passive"))
      (node (ref "R13") (pin "2") (pinfunction "2_2") (pintype "passive"))
      (node (ref "R2") (pin "1") (pinfunction "1_1") (pintype "passive"))
      (node (ref "R7") (pin "1") (pinfunction "1_1") (pintype "passive"))
      (node (ref "S1") (pin "1") (pintype "passive"))
      (node (ref "S2") (pin "1") (pintype "passive"))
      (node (ref "U1") (pin "17") (pinfunction "GND_17") (pintype "power_in"))
      (node (ref "U1") (pin "2") (pinfunction "GND_2") (pintype "power_in"))
      (node (ref "U1") (pin "46") (pinfunction "GND_46") (pintype "power_in"))
      (node (ref "U1") (pin "60") (pinfunction "GND_60") (pintype "power_in"))
      (node (ref "U4") (pin "2") (pinfunction "GND_2") (pintype "passive"))
      (node (ref "U5") (pin "2") (pinfunction "GND_2") (pintype "passive"))
    )
    (net (code "33") (name "Net-(C14-Pad1)") (class "Default")
      (node (ref "C14") (pin "1") (pinfunction "1_1") (pintype "passive"))
      (node (ref "R7") (pin "2") (pinfunction "2_2") (pintype "passive"))
    )
    (net (code "34") (name "Net-(DL1-K)") (class "Default")
      (node (ref "DL1") (pin "1") (pinfunction "K_1") (pintype "passive"))
      (node (ref "R6") (pin "2") (pinfunction "2_2") (pintype "passive"))
    )
    (net (code "35") (name "Net-(DL2-K)") (class "Default")
      (node (ref "DL2") (pin "1") (pinfunction "K_1") (pintype "passive"))
      (node (ref "R5") (pin "2") (pinfunction "2_2") (pintype "passive"))
    )
    (net (code "36") (name "Net-(J1-C1)") (class "Default")
      (node (ref "J1") (pin "1") (pinfunction "C1_1") (pintype "passive"))
      (node (ref "U1") (pin "31") (pinfunction "PA8/XOUT32/PGMM0_31") (pintype "bidirectional"))
    )
    (net (code "37") (name "Net-(J1-C2)") (class "Default")
      (node (ref "J1") (pin "2") (pinfunction "C2_2") (pintype "passive"))
      (node (ref "R12") (pin "1") (pinfunction "1_1") (pintype "passive"))
    )
    (net (code "38") (name "Net-(J2-C1)") (class "Default")
      (node (ref "J2") (pin "1") (pinfunction "C1_1") (pintype "passive"))
      (node (ref "U1") (pin "32") (pinfunction "PA7/XIN32/PGMNVALID_32") (pintype "bidirectional"))
    )
    (net (code "39") (name "Net-(J2-C2)") (class "Default")
      (node (ref "J2") (pin "2") (pinfunction "C2_2") (pintype "passive"))
      (node (ref "R13") (pin "1") (pinfunction "1_1") (pintype "passive"))
    )
    (net (code "40") (name "Net-(R14-Pad2)") (class "Default")
      (node (ref "R14") (pin "2") (pinfunction "2_2") (pintype "passive"))
      (node (ref "S1") (pin "2") (pintype "passive"))
    )
    (net (code "41") (name "Net-(R18-Pad2)") (class "Default")
      (node (ref "R18") (pin "2") (pinfunction "2_2") (pintype "passive"))
      (node (ref "S2") (pin "2") (pintype "passive"))
    )
    (net (code "42") (name "Net-(U1A-DDM{slash}PB10)") (class "Default")
      (node (ref "R4") (pin "2") (pinfunction "2_2") (pintype "passive"))
      (node (ref "U1") (pin "56") (pinfunction "DDM/PB10_56") (pintype "bidirectional"))
    )
    (net (code "43") (name "Net-(U1A-DDP{slash}PB11)") (class "Default")
      (node (ref "R3") (pin "2") (pinfunction "2_2") (pintype "passive"))
      (node (ref "U1") (pin "57") (pinfunction "DDP/PB11_57") (pintype "bidirectional"))
    )
    (net (code "44") (name "Net-(U1A-ERASE{slash}PB12)") (class "Default")
      (node (ref "ERASE") (pin "1") (pinfunction "1_1") (pintype "passive"))
      (node (ref "U1") (pin "55") (pinfunction "ERASE/PB12_55") (pintype "bidirectional"))
    )
    (net (code "45") (name "Net-(U1A-XIN{slash}PGMCK{slash}PB9)") (class "Default")
      (node (ref "C3") (pin "2") (pinfunction "2_2") (pintype "passive"))
      (node (ref "U1") (pin "62") (pinfunction "XIN/PGMCK/PB9_62") (pintype "bidirectional"))
      (node (ref "Y1") (pin "3") (pinfunction "OSC2_3") (pintype "passive"))
    )
    (net (code "46") (name "Net-(U1A-XOUT{slash}PB8)") (class "Default")
      (node (ref "C4") (pin "2") (pinfunction "2_2") (pintype "passive"))
      (node (ref "U1") (pin "61") (pinfunction "XOUT/PB8_61") (pintype "bidirectional"))
      (node (ref "Y1") (pin "1") (pinfunction "OSC1_1") (pintype "passive"))
    )
    (net (code "47") (name "Net-(U1B-VDDOUT)") (class "Default")
      (node (ref "C10") (pin "1") (pinfunction "1_1") (pintype "passive"))
      (node (ref "C12") (pin "1") (pinfunction "1_1") (pintype "passive"))
      (node (ref "C6") (pin "1") (pinfunction "1_1") (pintype "passive"))
      (node (ref "C8") (pin "1") (pinfunction "1_1") (pintype "passive"))
      (node (ref "L1") (pin "2") (pinfunction "2_2") (pintype "passive"))
      (node (ref "U1") (pin "12") (pinfunction "VDDCORE_12") (pintype "power_in"))
      (node (ref "U1") (pin "24") (pinfunction "VDDCORE_24") (pintype "power_in"))
      (node (ref "U1") (pin "54") (pinfunction "VDDCORE_54") (pintype "power_in"))
      (node (ref "U1") (pin "8") (pinfunction "VDDOUT_8") (pintype "power_in"))
    )
    (net (code "48") (name "Net-(U1B-VDDPLL)") (class "Default")
      (node (ref "C14") (pin "2") (pinfunction "2_2") (pintype "passive"))
      (node (ref "C15") (pin "1") (pinfunction "1_1") (pintype "passive"))
      (node (ref "L1") (pin "1") (pinfunction "1_1") (pintype "passive"))
      (node (ref "U1") (pin "64") (pinfunction "VDDPLL_64") (pintype "power_in"))
    )
    (net (code "49") (name "Net-(U4-DIR)") (class "Default")
      (node (ref "R32") (pin "1") (pinfunction "1_1") (pintype "passive"))
      (node (ref "U4") (pin "5") (pinfunction "DIR_5") (pintype "passive"))
    )
    (net (code "50") (name "Net-(U4-VCCA)") (class "Default")
      (node (ref "C28") (pin "2") (pinfunction "2_2") (pintype "passive"))
      (node (ref "R27") (pin "2") (pinfunction "2_2") (pintype "passive"))
      (node (ref "U4") (pin "1") (pinfunction "VCCA_1") (pintype "passive"))
    )
    (net (code "51") (name "Net-(U4-VCCB)") (class "Default")
      (node (ref "C41") (pin "2") (pinfunction "2_2") (pintype "passive"))
      (node (ref "R28") (pin "1") (pinfunction "1_1") (pintype "passive"))
      (node (ref "U4") (pin "6") (pinfunction "VCCB_6") (pintype "passive"))
    )
    (net (code "52") (name "Net-(U5-DIR)") (class "Default")
      (node (ref "R33") (pin "1") (pinfunction "1_1") (pintype "passive"))
      (node (ref "U5") (pin "5") (pinfunction "DIR_5") (pintype "passive"))
    )
    (net (code "53") (name "Net-(U5-VCCA)") (class "Default")
      (node (ref "C40") (pin "2") (pinfunction "2_2") (pintype "passive"))
      (node (ref "R15") (pin "2") (pinfunction "2_2") (pintype "passive"))
      (node (ref "U5") (pin "1") (pinfunction "VCCA_1") (pintype "passive"))
    )
    (net (code "54") (name "Net-(U5-VCCB)") (class "Default")
      (node (ref "C29") (pin "2") (pinfunction "2_2") (pintype "passive"))
      (node (ref "R16") (pin "1") (pinfunction "1_1") (pintype "passive"))
      (node (ref "U5") (pin "6") (pinfunction "VCCB_6") (pintype "passive"))
    )
    (net (code "55") (name "VBAT_RAW") (class "Default")
      (node (ref "R9") (pin "2") (pinfunction "2_2") (pintype "passive"))
    )
    (net (code "56") (name "VBUS") (class "Default")
      (node (ref "H1") (pin "1") (pinfunction "VBUS_1") (pintype "power_in"))
      (node (ref "R1") (pin "2") (pinfunction "2_2") (pintype "passive"))
    )
    (net (code "57") (name "unconnected-(H1-ID-Pad4)") (class "Default")
      (node (ref "H1") (pin "4") (pinfunction "ID_4") (pintype "power_in+no_connect"))
    )
    (net (code "58") (name "unconnected-(H2-Pad3)") (class "Default")
      (node (ref "H2") (pin "3") (pinfunction "3_3") (pintype "passive+no_connect"))
    )
    (net (code "59") (name "unconnected-(H2-Pad9)") (class "Default")
      (node (ref "H2") (pin "9") (pinfunction "9_9") (pintype "passive+no_connect"))
    )
    (net (code "60") (name "unconnected-(H2-Pad10)") (class "Default")
      (node (ref "H2") (pin "10") (pinfunction "10_10") (pintype "passive+no_connect"))
    )
    (net (code "61") (name "unconnected-(U1A-JTAGSEL-Pad50)") (class "Default")
      (node (ref "U1") (pin "50") (pinfunction "JTAGSEL_50") (pintype "input+no_connect"))
    )
    (net (code "62") (name "unconnected-(U1A-PA0{slash}PGMEN0-Pad48)") (class "Default")
      (node (ref "U1") (pin "48") (pinfunction "PA0/PGMEN0_48") (pintype "bidirectional"))
    )
    (net (code "63") (name "unconnected-(U1A-PA1{slash}PGMEN1-Pad47)") (class "Default")
      (node (ref "U1") (pin "47") (pinfunction "PA1/PGMEN1_47") (pintype "bidirectional"))
    )
    (net (code "64") (name "unconnected-(U1A-PA2{slash}PGMEN2-Pad44)") (class "Default")
      (node (ref "U1") (pin "44") (pinfunction "PA2/PGMEN2_44") (pintype "bidirectional"))
    )
    (net (code "65") (name "unconnected-(U1A-PA5{slash}PGMRDY-Pad35)") (class "Default")
      (node (ref "U1") (pin "35") (pinfunction "PA5/PGMRDY_35") (pintype "bidirectional"))
    )
    (net (code "66") (name "unconnected-(U1A-PA6{slash}PGMNOE-Pad34)") (class "Default")
      (node (ref "U1") (pin "34") (pinfunction "PA6/PGMNOE_34") (pintype "bidirectional"))
    )
    (net (code "67") (name "unconnected-(U1A-PA17{slash}PGMD5{slash}AD0-Pad9)") (class "Default")
      (node (ref "U1") (pin "9") (pinfunction "PA17/PGMD5/AD0_9") (pintype "bidirectional"))
    )
    (net (code "68") (name "unconnected-(U1A-PA19{slash}PGMD7{slash}AD2-Pad13)") (class "Default")
      (node (ref "U1") (pin "13") (pinfunction "PA19/PGMD7/AD2_13") (pintype "bidirectional"))
    )
    (net (code "69") (name "unconnected-(U1A-PA21{slash}PGMD9{slash}AD8-Pad11)") (class "Default")
      (node (ref "U1") (pin "11") (pinfunction "PA21/PGMD9/AD8_11") (pintype "bidirectional"))
    )
    (net (code "70") (name "unconnected-(U1A-PA22{slash}PGMD10{slash}AD9-Pad14)") (class "Default")
      (node (ref "U1") (pin "14") (pinfunction "PA22/PGMD10/AD9_14") (pintype "bidirectional"))
    )
    (net (code "71") (name "unconnected-(U1A-PA25{slash}PGMD13-Pad25)") (class "Default")
      (node (ref "U1") (pin "25") (pinfunction "PA25/PGMD13_25") (pintype "bidirectional"))
    )
    (net (code "72") (name "unconnected-(U1A-PA26{slash}PGMD14-Pad26)") (class "Default")
      (node (ref "U1") (pin "26") (pinfunction "PA26/PGMD14_26") (pintype "bidirectional"))
    )
    (net (code "73") (name "unconnected-(U1A-PA29-Pad41)") (class "Default")
      (node (ref "U1") (pin "41") (pinfunction "PA29_41") (pintype "bidirectional"))
    )
    (net (code "74") (name "unconnected-(U1A-PA30-Pad42)") (class "Default")
      (node (ref "U1") (pin "42") (pinfunction "PA30_42") (pintype "bidirectional"))
    )
    (net (code "75") (name "unconnected-(U1A-PB13{slash}DAC0-Pad59)") (class "Default")
      (node (ref "U1") (pin "59") (pinfunction "PB13/DAC0_59") (pintype "bidirectional"))
    )
    (net (code "76") (name "unconnected-(U1A-PB14{slash}DAC1-Pad63)") (class "Default")
      (node (ref "U1") (pin "63") (pinfunction "PB14/DAC1_63") (pintype "bidirectional"))
    )
    (net (code "77") (name "unconnected-(U1A-TDI{slash}PB4-Pad33)") (class "Default")
      (node (ref "U1") (pin "33") (pinfunction "TDI/PB4_33") (pintype "bidirectional"))
    )
    (net (code "78") (name "unconnected-(U1A-TDO{slash}TRACESWO{slash}PB5-Pad49)") (class "Default")
      (node (ref "U1") (pin "49") (pinfunction "TDO/TRACESWO/PB5_49") (pintype "bidirectional"))
    )
    (net (code "79") (name "unconnected-(U1A-TST-Pad40)") (class "Default")
      (node (ref "U1") (pin "40") (pinfunction "TST_40") (pintype "input+no_connect"))
    )
  )
)
